# UV-LED.net
KiCad netlist of a schematic drawn in Altium Designer
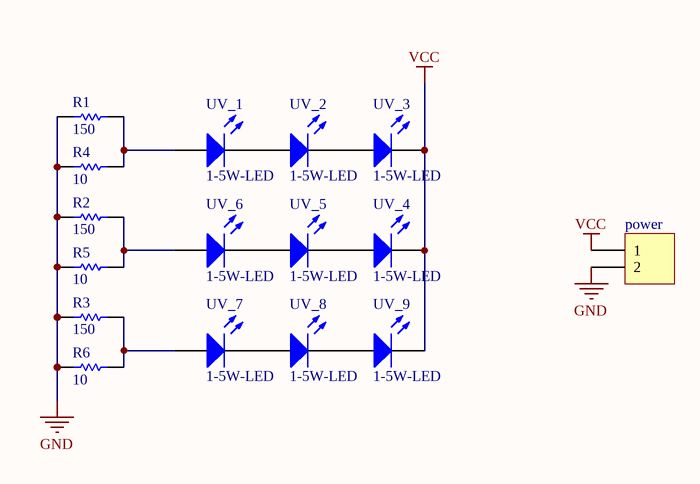
[diagram p0: UV-LED.SchDoc]

(export (version "E")
  (design (tool "Eeschema 10.0.6"))
  (components
    (comp (ref "power")
      (value "Header 2")
      (footprint "HDR1X2")
      (description "Header, 2-Pin")
      (fields (field (name "PUBLISHER") "Altium Limited"))
      (libsource (lib "Miscellaneous Connectors") (part "Header 2"))
    )
    (comp (ref "R1")
      (value "150")
      (footprint "AXIAL-0.3")
      (description "Resistor")
      (fields (field (name "Comment") "Res1") (field (name "PUBLISHER") "Altium Limited"))
      (libsource (lib "Miscellaneous Devices") (part "Res1"))
    )
    (comp (ref "R2")
      (value "150")
      (footprint "AXIAL-0.3")
      (description "Resistor")
      (fields (field (name "Comment") "Res1") (field (name "PUBLISHER") "Altium Limited"))
      (libsource (lib "Miscellaneous Devices") (part "Res1"))
    )
    (comp (ref "R3")
      (value "150")
      (footprint "AXIAL-0.3")
      (description "Resistor")
      (fields (field (name "Comment") "Res1") (field (name "PUBLISHER") "Altium Limited"))
      (libsource (lib "Miscellaneous Devices") (part "Res1"))
    )
    (comp (ref "R4")
      (value "10")
      (footprint "AXIAL-0.3")
      (description "Resistor")
      (fields (field (name "Comment") "Res1") (field (name "PUBLISHER") "Altium Limited"))
      (libsource (lib "Miscellaneous Devices") (part "Res1"))
    )
    (comp (ref "R5")
      (value "10")
      (footprint "AXIAL-0.3")
      (description "Resistor")
      (fields (field (name "Comment") "Res1") (field (name "PUBLISHER") "Altium Limited"))
      (libsource (lib "Miscellaneous Devices") (part "Res1"))
    )
    (comp (ref "R6")
      (value "10")
      (footprint "AXIAL-0.3")
      (description "Resistor")
      (fields (field (name "Comment") "Res1") (field (name "PUBLISHER") "Altium Limited"))
      (libsource (lib "Miscellaneous Devices") (part "Res1"))
    )
    (comp (ref "UV_1")
      (value "1-5W-LED")
      (footprint "Highpwr_SMT_LED")
      (libsource (lib "arad") (part "1-5W-LED"))
    )
    (comp (ref "UV_2")
      (value "1-5W-LED")
      (footprint "Highpwr_SMT_LED")
      (libsource (lib "arad") (part "1-5W-LED"))
    )
    (comp (ref "UV_3")
      (value "1-5W-LED")
      (footprint "Highpwr_SMT_LED")
      (libsource (lib "arad") (part "1-5W-LED"))
    )
    (comp (ref "UV_4")
      (value "1-5W-LED")
      (footprint "Highpwr_SMT_LED")
      (libsource (lib "arad") (part "1-5W-LED"))
    )
    (comp (ref "UV_5")
      (value "1-5W-LED")
      (footprint "Highpwr_SMT_LED")
      (libsource (lib "arad") (part "1-5W-LED"))
    )
    (comp (ref "UV_6")
      (value "1-5W-LED")
      (footprint "Highpwr_SMT_LED")
      (libsource (lib "arad") (part "1-5W-LED"))
    )
    (comp (ref "UV_7")
      (value "1-5W-LED")
      (footprint "Highpwr_SMT_LED")
      (libsource (lib "arad") (part "1-5W-LED"))
    )
    (comp (ref "UV_8")
      (value "1-5W-LED")
      (footprint "Highpwr_SMT_LED")
      (libsource (lib "arad") (part "1-5W-LED"))
    )
    (comp (ref "UV_9")
      (value "1-5W-LED")
      (footprint "Highpwr_SMT_LED")
      (libsource (lib "arad") (part "1-5W-LED"))
    )
  )
  (nets
    (net (code "1") (name "GND") (class "Default")
      (node (ref "R1") (pin "1") (pinfunction "1_1") (pintype "passive"))
      (node (ref "R2") (pin "1") (pinfunction "1_1") (pintype "passive"))
      (node (ref "R3") (pin "1") (pinfunction "1_1") (pintype "passive"))
      (node (ref "R4") (pin "1") (pinfunction "1_1") (pintype "passive"))
      (node (ref "R5") (pin "1") (pinfunction "1_1") (pintype "passive"))
      (node (ref "R6") (pin "1") (pinfunction "1_1") (pintype "passive"))
      (node (ref "power") (pin "2") (pinfunction "2_2") (pintype "passive"))
    )
    (net (code "2") (name "Net-(UV_1-A)") (class "Default")
      (node (ref "R1") (pin "2") (pinfunction "2_2") (pintype "passive"))
      (node (ref "R4") (pin "2") (pinfunction "2_2") (pintype "passive"))
      (node (ref "UV_1") (pin "1") (pinfunction "A_1") (pintype "passive"))
    )
    (net (code "3") (name "Net-(UV_1-K)") (class "Default")
      (node (ref "UV_1") (pin "2") (pinfunction "K_2") (pintype "passive"))
      (node (ref "UV_2") (pin "1") (pinfunction "A_1") (pintype "passive"))
    )
    (net (code "4") (name "Net-(UV_2-K)") (class "Default")
      (node (ref "UV_2") (pin "2") (pinfunction "K_2") (pintype "passive"))
      (node (ref "UV_3") (pin "1") (pinfunction "A_1") (pintype "passive"))
    )
    (net (code "5") (name "Net-(UV_4-A)") (class "Default")
      (node (ref "UV_4") (pin "1") (pinfunction "A_1") (pintype "passive"))
      (node (ref "UV_5") (pin "2") (pinfunction "K_2") (pintype "passive"))
    )
    (net (code "6") (name "Net-(UV_5-A)") (class "Default")
      (node (ref "UV_5") (pin "1") (pinfunction "A_1") (pintype "passive"))
      (node (ref "UV_6") (pin "2") (pinfunction "K_2") (pintype "passive"))
    )
    (net (code "7") (name "Net-(UV_6-A)") (class "Default")
      (node (ref "R2") (pin "2") (pinfunction "2_2") (pintype "passive"))
      (node (ref "R5") (pin "2") (pinfunction "2_2") (pintype "passive"))
      (node (ref "UV_6") (pin "1") (pinfunction "A_1") (pintype "passive"))
    )
    (net (code "8") (name "Net-(UV_7-A)") (class "Default")
      (node (ref "R3") (pin "2") (pinfunction "2_2") (pintype "passive"))
      (node (ref "R6") (pin "2") (pinfunction "2_2") (pintype "passive"))
      (node (ref "UV_7") (pin "1") (pinfunction "A_1") (pintype "passive"))
    )
    (net (code "9") (name "Net-(UV_7-K)") (class "Default")
      (node (ref "UV_7") (pin "2") (pinfunction "K_2") (pintype "passive"))
      (node (ref "UV_8") (pin "1") (pinfunction "A_1") (pintype "passive"))
    )
    (net (code "10") (name "Net-(UV_8-K)") (class "Default")
      (node (ref "UV_8") (pin "2") (pinfunction "K_2") (pintype "passive"))
      (node (ref "UV_9") (pin "1") (pinfunction "A_1") (pintype "passive"))
    )
    (net (code "11") (name "VCC") (class "Default")
      (node (ref "UV_3") (pin "2") (pinfunction "K_2") (pintype "passive"))
      (node (ref "UV_4") (pin "2") (pinfunction "K_2") (pintype "passive"))
      (node (ref "UV_9") (pin "2") (pinfunction "K_2") (pintype "passive"))
      (node (ref "power") (pin "1") (pinfunction "1_1") (pintype "passive"))
    )
  )
)
